# ReboostV2_MC.net
KiCad netlist of a schematic drawn in Altium Designer
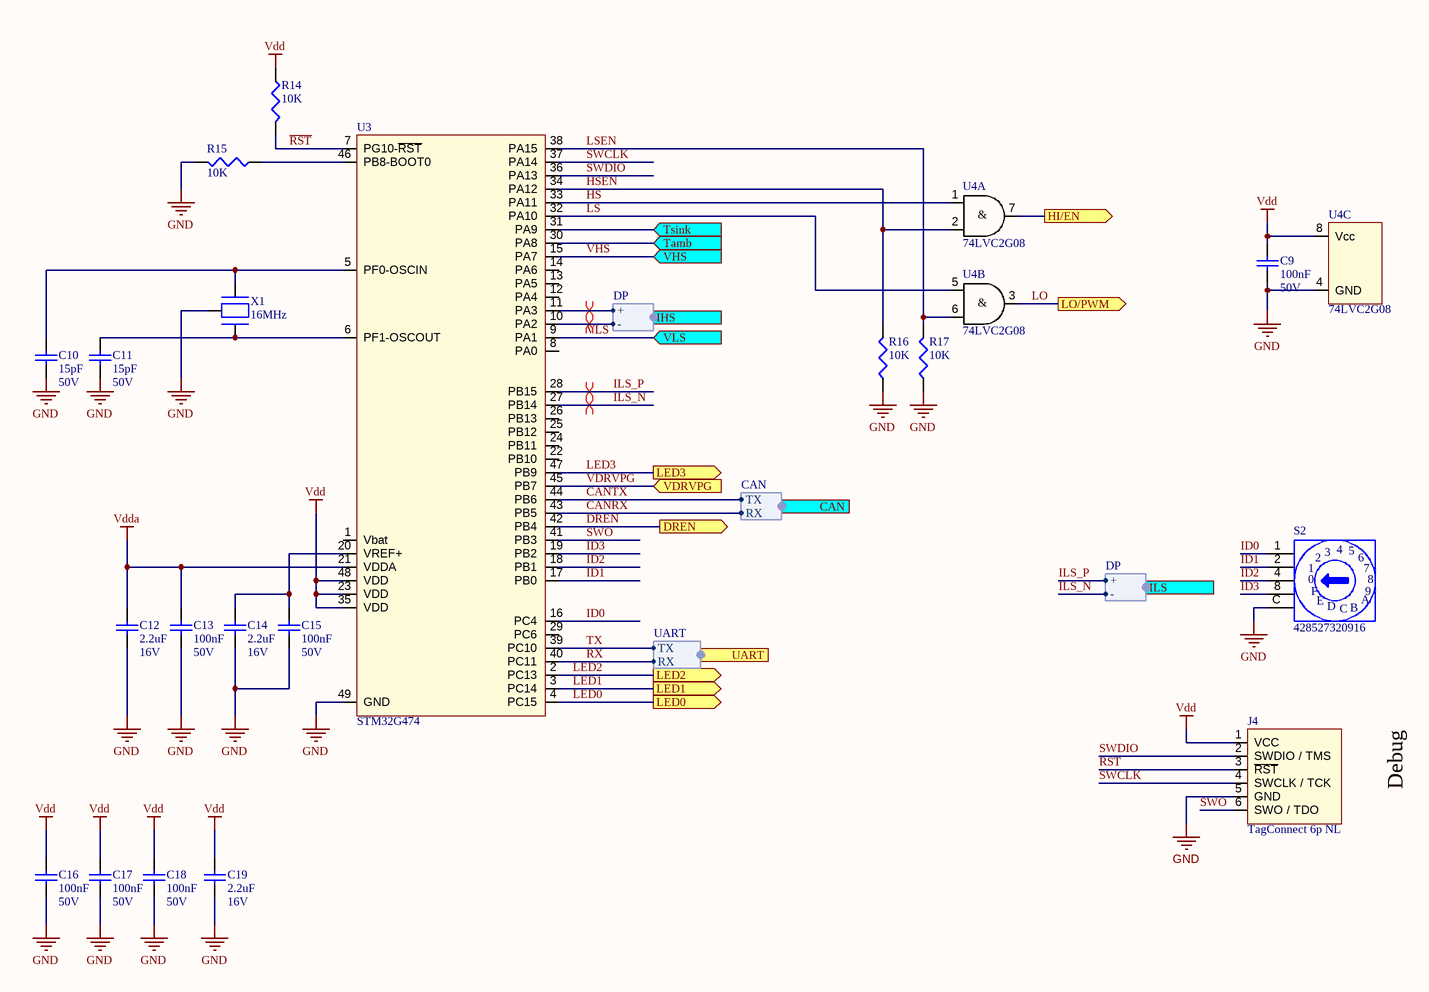
[diagram p0: ReboostV2_MC.SchDoc]

(export (version "E")
  (design (tool "Eeschema 10.0.6"))
  (components
    (comp (ref "C9")
      (value "100nF")
      (footprint "C0603")
      (description "Capacitor, 100nF, 50V, X7R")
      (fields (field (name "VOLTAGE RATING") "50V"))
      (libsource (lib "AR_Capacitors_Ceramic") (part "100nF/0603/CER/50V"))
    )
    (comp (ref "C10")
      (value "15pF")
      (footprint "C0603")
      (description "Capacitor, 15pF, 50V, C0G / NP0")
      (fields (field (name "VOLTAGE RATING") "50V"))
      (libsource (lib "AR_Capacitors_Ceramic") (part "15pF/0603/CER/50V"))
    )
    (comp (ref "C11")
      (value "15pF")
      (footprint "C0603")
      (description "Capacitor, 15pF, 50V, C0G / NP0")
      (fields (field (name "VOLTAGE RATING") "50V"))
      (libsource (lib "AR_Capacitors_Ceramic") (part "15pF/0603/CER/50V"))
    )
    (comp (ref "C12")
      (value "2.2uF")
      (footprint "C0603")
      (description "Capacitor, 2.2uF, 16V, X5R")
      (fields (field (name "VOLTAGE RATING") "16V"))
      (libsource (lib "AR_Capacitors_Ceramic") (part "2.2uF/0603/CER/16V"))
    )
    (comp (ref "C13")
      (value "100nF")
      (footprint "C0603")
      (description "Capacitor, 100nF, 50V, X7R")
      (fields (field (name "VOLTAGE RATING") "50V"))
      (libsource (lib "AR_Capacitors_Ceramic") (part "100nF/0603/CER/50V"))
    )
    (comp (ref "C14")
      (value "2.2uF")
      (footprint "C0603")
      (description "Capacitor, 2.2uF, 16V, X5R")
      (fields (field (name "VOLTAGE RATING") "16V"))
      (libsource (lib "AR_Capacitors_Ceramic") (part "2.2uF/0603/CER/16V"))
    )
    (comp (ref "C15")
      (value "100nF")
      (footprint "C0603")
      (description "Capacitor, 100nF, 50V, X7R")
      (fields (field (name "VOLTAGE RATING") "50V"))
      (libsource (lib "AR_Capacitors_Ceramic") (part "100nF/0603/CER/50V"))
    )
    (comp (ref "C16")
      (value "100nF")
      (footprint "C0603")
      (description "Capacitor, 100nF, 50V, X7R")
      (fields (field (name "VOLTAGE RATING") "50V"))
      (libsource (lib "AR_Capacitors_Ceramic") (part "100nF/0603/CER/50V"))
    )
    (comp (ref "C17")
      (value "100nF")
      (footprint "C0603")
      (description "Capacitor, 100nF, 50V, X7R")
      (fields (field (name "VOLTAGE RATING") "50V"))
      (libsource (lib "AR_Capacitors_Ceramic") (part "100nF/0603/CER/50V"))
    )
    (comp (ref "C18")
      (value "100nF")
      (footprint "C0603")
      (description "Capacitor, 100nF, 50V, X7R")
      (fields (field (name "VOLTAGE RATING") "50V"))
      (libsource (lib "AR_Capacitors_Ceramic") (part "100nF/0603/CER/50V"))
    )
    (comp (ref "C19")
      (value "2.2uF")
      (footprint "C0603")
      (description "Capacitor, 2.2uF, 16V, X5R")
      (fields (field (name "VOLTAGE RATING") "16V"))
      (libsource (lib "AR_Capacitors_Ceramic") (part "2.2uF/0603/CER/16V"))
    )
    (comp (ref "J4")
      (value "TagConnect 6p NL")
      (footprint "TC2030-IDC-NL")
      (description "“No Legs” 6-pin Plug-of-Nails™ Cable fitted with a 6-pin 0.1″ pitch ribbon connector.")
      (libsource (lib "AR_Connectors") (part "TC2030-IDC"))
    )
    (comp (ref "R14")
      (value "10K")
      (footprint "0603")
      (description "Resistor, 10K, 1%, 0.063W, 50V, 100PPM, 0603")
      (libsource (lib "AR_Resistors_SMD") (part "10K/0603/0063W/50V"))
    )
    (comp (ref "R15")
      (value "10K")
      (footprint "0603")
      (description "Resistor, 10K, 1%, 0.063W, 50V, 100PPM, 0603")
      (libsource (lib "AR_Resistors_SMD") (part "10K/0603/0063W/50V"))
    )
    (comp (ref "R16")
      (value "10K")
      (footprint "0603")
      (description "Resistor, 10K, 1%, 0.063W, 50V, 100PPM, 0603")
      (libsource (lib "AR_Resistors_SMD") (part "10K/0603/0063W/50V"))
    )
    (comp (ref "R17")
      (value "10K")
      (footprint "0603")
      (description "Resistor, 10K, 1%, 0.063W, 50V, 100PPM, 0603")
      (libsource (lib "AR_Resistors_SMD") (part "10K/0603/0063W/50V"))
    )
    (comp (ref "S2")
      (value "428527320916")
      (footprint "42852732091x_16p")
      (description "WS-ROTV THT Rotary Switch with Arrow Type Actuator, 10x10mm, 16 positions")
      (fields (field (name "PUBLISHER") "Wurth Elektronik"))
      (libsource (lib "Altium_WS-ROTV (rev19a)") (part "428527320916"))
    )
    (comp (ref "U3")
      (value "STM32G474")
      (footprint "QFN48")
      (description "ARM MCU, STM32 Family STM32G4 Series Microcontrollers, ARM Cortex-M4F, 32bit, 170 MHz, 512 KB")
      (libsource (lib "AR_Microcontrollers") (part "STM32G474CEU6"))
    )
    (comp (ref "U4")
      (value "74LVC2G08")
      (footprint "TSSOP8")
      (description "Dual 2-input AND gate")
      (libsource (lib "AR_ICs") (part "74LVC2G08"))
    )
    (comp (ref "X1")
      (value "16MHz")
      (footprint "7M")
      (description "CRYSTAL, 16MHz,18PF CL, 3.2X2.5MM SMT")
      (libsource (lib "AR_Crystals") (part "7M-16.000MAAJ-T"))
    )
  )
  (nets
    (net (code "4") (name "/CANRX") (class "Default")
      (node (ref "U3") (pin "43") (pinfunction "PB5_43") (pintype "passive"))
    )
    (net (code "5") (name "/CANTX") (class "Default")
      (node (ref "U3") (pin "44") (pinfunction "PB6_44") (pintype "passive"))
    )
    (net (code "6") (name "/DREN") (class "Default")
      (node (ref "U3") (pin "42") (pinfunction "PB4_42") (pintype "passive"))
    )
    (net (code "7") (name "/HI{slash}EN") (class "Default")
      (node (ref "U4") (pin "7") (pinfunction "Y_7") (pintype "passive"))
    )
    (net (code "8") (name "/HS") (class "Default")
      (node (ref "U3") (pin "33") (pinfunction "PA11_33") (pintype "passive"))
      (node (ref "U4") (pin "1") (pinfunction "A_1") (pintype "passive"))
    )
    (net (code "9") (name "/HSEN") (class "Default")
      (node (ref "R16") (pin "2") (pinfunction "2_2") (pintype "passive"))
      (node (ref "U3") (pin "34") (pinfunction "PA12_34") (pintype "passive"))
      (node (ref "U4") (pin "2") (pinfunction "B_2") (pintype "passive"))
    )
    (net (code "10") (name "/ID0") (class "Default")
      (node (ref "S2") (pin "1") (pinfunction "1_1") (pintype "passive"))
      (node (ref "U3") (pin "16") (pinfunction "PC4_16") (pintype "passive"))
    )
    (net (code "11") (name "/ID1") (class "Default")
      (node (ref "S2") (pin "2") (pinfunction "2_2") (pintype "passive"))
      (node (ref "U3") (pin "17") (pinfunction "PB0_17") (pintype "passive"))
    )
    (net (code "12") (name "/ID2") (class "Default")
      (node (ref "S2") (pin "4") (pinfunction "4_4") (pintype "passive"))
      (node (ref "U3") (pin "18") (pinfunction "PB1_18") (pintype "passive"))
    )
    (net (code "13") (name "/ID3") (class "Default")
      (node (ref "S2") (pin "8") (pinfunction "8_8") (pintype "passive"))
      (node (ref "U3") (pin "19") (pinfunction "PB2_19") (pintype "passive"))
    )
    (net (code "14") (name "/ILS_N") (class "Default")
      (node (ref "U3") (pin "27") (pinfunction "PB14_27") (pintype "passive"))
    )
    (net (code "15") (name "/ILS_P") (class "Default")
      (node (ref "U3") (pin "28") (pinfunction "PB15_28") (pintype "passive"))
    )
    (net (code "16") (name "/LED0") (class "Default")
      (node (ref "U3") (pin "4") (pinfunction "PC15_4") (pintype "passive"))
    )
    (net (code "17") (name "/LED1") (class "Default")
      (node (ref "U3") (pin "3") (pinfunction "PC14_3") (pintype "passive"))
    )
    (net (code "18") (name "/LED2") (class "Default")
      (node (ref "U3") (pin "2") (pinfunction "PC13_2") (pintype "passive"))
    )
    (net (code "19") (name "/LED3") (class "Default")
      (node (ref "U3") (pin "47") (pinfunction "PB9_47") (pintype "passive"))
    )
    (net (code "20") (name "/LO") (class "Default")
      (node (ref "U4") (pin "3") (pinfunction "Y_3") (pintype "passive"))
    )
    (net (code "21") (name "/LS") (class "Default")
      (node (ref "U3") (pin "32") (pinfunction "PA10_32") (pintype "passive"))
      (node (ref "U4") (pin "5") (pinfunction "A_5") (pintype "passive"))
    )
    (net (code "22") (name "/LSEN") (class "Default")
      (node (ref "R17") (pin "2") (pinfunction "2_2") (pintype "passive"))
      (node (ref "U3") (pin "38") (pinfunction "PA15_38") (pintype "passive"))
      (node (ref "U4") (pin "6") (pinfunction "B_6") (pintype "passive"))
    )
    (net (code "23") (name "/RX") (class "Default")
      (node (ref "U3") (pin "40") (pinfunction "PC11_40") (pintype "passive"))
    )
    (net (code "24") (name "/SWCLK") (class "Default")
      (node (ref "J4") (pin "4") (pinfunction "SWCLK_/_TCK_4") (pintype "passive"))
      (node (ref "U3") (pin "37") (pinfunction "PA14_37") (pintype "passive"))
    )
    (net (code "25") (name "/SWDIO") (class "Default")
      (node (ref "J4") (pin "2") (pinfunction "SWDIO_/_TMS_2") (pintype "passive"))
      (node (ref "U3") (pin "36") (pinfunction "PA13_36") (pintype "passive"))
    )
    (net (code "26") (name "/SWO") (class "Default")
      (node (ref "J4") (pin "6") (pinfunction "SWO_/_TDO_6") (pintype "passive"))
      (node (ref "U3") (pin "41") (pinfunction "PB3_41") (pintype "passive"))
    )
    (net (code "27") (name "/TX") (class "Default")
      (node (ref "U3") (pin "39") (pinfunction "PC10_39") (pintype "passive"))
    )
    (net (code "28") (name "/Tamb") (class "Default")
      (node (ref "U3") (pin "30") (pinfunction "PA8_30") (pintype "passive"))
    )
    (net (code "29") (name "/Tsink") (class "Default")
      (node (ref "U3") (pin "31") (pinfunction "PA9_31") (pintype "passive"))
    )
    (net (code "30") (name "/VDRVPG") (class "Default")
      (node (ref "U3") (pin "45") (pinfunction "PB7_45") (pintype "passive"))
    )
    (net (code "31") (name "/VHS") (class "Default")
      (node (ref "U3") (pin "15") (pinfunction "PA7_15") (pintype "passive"))
    )
    (net (code "32") (name "/VLS") (class "Default")
      (node (ref "U3") (pin "9") (pinfunction "PA1_9") (pintype "passive"))
    )
    (net (code "36") (name "/~{RST}") (class "Default")
      (node (ref "J4") (pin "3") (pinfunction "~{RST}_3") (pintype "passive"))
      (node (ref "R14") (pin "2") (pinfunction "2_2") (pintype "passive"))
      (node (ref "U3") (pin "7") (pinfunction "PG10-~{RST}_7") (pintype "passive"))
    )
    (net (code "37") (name "GND") (class "Default")
      (node (ref "C10") (pin "1") (pinfunction "1_1") (pintype "passive"))
      (node (ref "C11") (pin "1") (pinfunction "1_1") (pintype "passive"))
      (node (ref "C12") (pin "1") (pinfunction "1_1") (pintype "passive"))
      (node (ref "C13") (pin "1") (pinfunction "1_1") (pintype "passive"))
      (node (ref "C14") (pin "1") (pinfunction "1_1") (pintype "passive"))
      (node (ref "C15") (pin "1") (pinfunction "1_1") (pintype "passive"))
      (node (ref "C16") (pin "1") (pinfunction "1_1") (pintype "passive"))
      (node (ref "C17") (pin "1") (pinfunction "1_1") (pintype "passive"))
      (node (ref "C18") (pin "1") (pinfunction "1_1") (pintype "passive"))
      (node (ref "C19") (pin "1") (pinfunction "1_1") (pintype "passive"))
      (node (ref "C9") (pin "1") (pinfunction "1_1") (pintype "passive"))
      (node (ref "J4") (pin "5") (pinfunction "GND_5") (pintype "passive"))
      (node (ref "R15") (pin "2") (pinfunction "2_2") (pintype "passive"))
      (node (ref "R16") (pin "1") (pinfunction "1_1") (pintype "passive"))
      (node (ref "R17") (pin "1") (pinfunction "1_1") (pintype "passive"))
      (node (ref "S2") (pin "C") (pinfunction "C_C") (pintype "passive"))
      (node (ref "U3") (pin "49") (pinfunction "GND_49") (pintype "passive"))
      (node (ref "U4") (pin "4") (pinfunction "GND_4") (pintype "passive"))
      (node (ref "X1") (pin "0") (pinfunction "0_0") (pintype "power_in"))
    )
    (net (code "38") (name "Net-(U3-PB8-BOOT0)") (class "Default")
      (node (ref "R15") (pin "1") (pinfunction "1_1") (pintype "passive"))
      (node (ref "U3") (pin "46") (pinfunction "PB8-BOOT0_46") (pintype "passive"))
    )
    (net (code "39") (name "Net-(U3-PF0-OSCIN)") (class "Default")
      (node (ref "C10") (pin "2") (pinfunction "2_2") (pintype "passive"))
      (node (ref "U3") (pin "5") (pinfunction "PF0-OSCIN_5") (pintype "passive"))
      (node (ref "X1") (pin "1") (pinfunction "1_1") (pintype "passive"))
    )
    (net (code "40") (name "Net-(U3-PF1-OSCOUT)") (class "Default")
      (node (ref "C11") (pin "2") (pinfunction "2_2") (pintype "passive"))
      (node (ref "U3") (pin "6") (pinfunction "PF1-OSCOUT_6") (pintype "passive"))
      (node (ref "X1") (pin "2") (pinfunction "2_2") (pintype "passive"))
    )
    (net (code "41") (name "Net-(U3-VREF+)") (class "Default")
      (node (ref "C14") (pin "2") (pinfunction "2_2") (pintype "passive"))
      (node (ref "C15") (pin "2") (pinfunction "2_2") (pintype "passive"))
      (node (ref "U3") (pin "20") (pinfunction "VREF+_20") (pintype "passive"))
    )
    (net (code "42") (name "Vdd") (class "Default")
      (node (ref "C16") (pin "2") (pinfunction "2_2") (pintype "passive"))
      (node (ref "C17") (pin "2") (pinfunction "2_2") (pintype "passive"))
      (node (ref "C18") (pin "2") (pinfunction "2_2") (pintype "passive"))
      (node (ref "C19") (pin "2") (pinfunction "2_2") (pintype "passive"))
      (node (ref "C9") (pin "2") (pinfunction "2_2") (pintype "passive"))
      (node (ref "J4") (pin "1") (pinfunction "VCC_1") (pintype "passive"))
      (node (ref "R14") (pin "1") (pinfunction "1_1") (pintype "passive"))
      (node (ref "U3") (pin "23") (pinfunction "VDD_23") (pintype "passive"))
      (node (ref "U3") (pin "35") (pinfunction "VDD_35") (pintype "passive"))
      (node (ref "U3") (pin "48") (pinfunction "VDD_48") (pintype "passive"))
      (node (ref "U4") (pin "8") (pinfunction "Vcc_8") (pintype "passive"))
    )
    (net (code "43") (name "Vdda") (class "Default")
      (node (ref "C12") (pin "2") (pinfunction "2_2") (pintype "passive"))
      (node (ref "C13") (pin "2") (pinfunction "2_2") (pintype "passive"))
      (node (ref "U3") (pin "21") (pinfunction "VDDA_21") (pintype "passive"))
    )
    (net (code "44") (name "unconnected-(U3-PA0-Pad8)") (class "Default")
      (node (ref "U3") (pin "8") (pinfunction "PA0_8") (pintype "passive"))
    )
    (net (code "45") (name "unconnected-(U3-PA2-Pad10)") (class "Default")
      (node (ref "U3") (pin "10") (pinfunction "PA2_10") (pintype "passive"))
    )
    (net (code "46") (name "unconnected-(U3-PA3-Pad11)") (class "Default")
      (node (ref "U3") (pin "11") (pinfunction "PA3_11") (pintype "passive"))
    )
    (net (code "47") (name "unconnected-(U3-PA4-Pad12)") (class "Default")
      (node (ref "U3") (pin "12") (pinfunction "PA4_12") (pintype "passive"))
    )
    (net (code "48") (name "unconnected-(U3-PA5-Pad13)") (class "Default")
      (node (ref "U3") (pin "13") (pinfunction "PA5_13") (pintype "passive"))
    )
    (net (code "49") (name "unconnected-(U3-PA6-Pad14)") (class "Default")
      (node (ref "U3") (pin "14") (pinfunction "PA6_14") (pintype "passive"))
    )
    (net (code "50") (name "unconnected-(U3-PB10-Pad22)") (class "Default")
      (node (ref "U3") (pin "22") (pinfunction "PB10_22") (pintype "passive"))
    )
    (net (code "51") (name "unconnected-(U3-PB11-Pad24)") (class "Default")
      (node (ref "U3") (pin "24") (pinfunction "PB11_24") (pintype "passive"))
    )
    (net (code "52") (name "unconnected-(U3-PB12-Pad25)") (class "Default")
      (node (ref "U3") (pin "25") (pinfunction "PB12_25") (pintype "passive"))
    )
    (net (code "53") (name "unconnected-(U3-PB13-Pad26)") (class "Default")
      (node (ref "U3") (pin "26") (pinfunction "PB13_26") (pintype "passive"))
    )
    (net (code "54") (name "unconnected-(U3-PC6-Pad29)") (class "Default")
      (node (ref "U3") (pin "29") (pinfunction "PC6_29") (pintype "passive"))
    )
    (net (code "55") (name "unconnected-(U3-Vbat-Pad1)") (class "Default")
      (node (ref "U3") (pin "1") (pinfunction "Vbat_1") (pintype "passive"))
    )
  )
)
